# Thermistor.net
KiCad netlist of a schematic drawn in Altium Designer
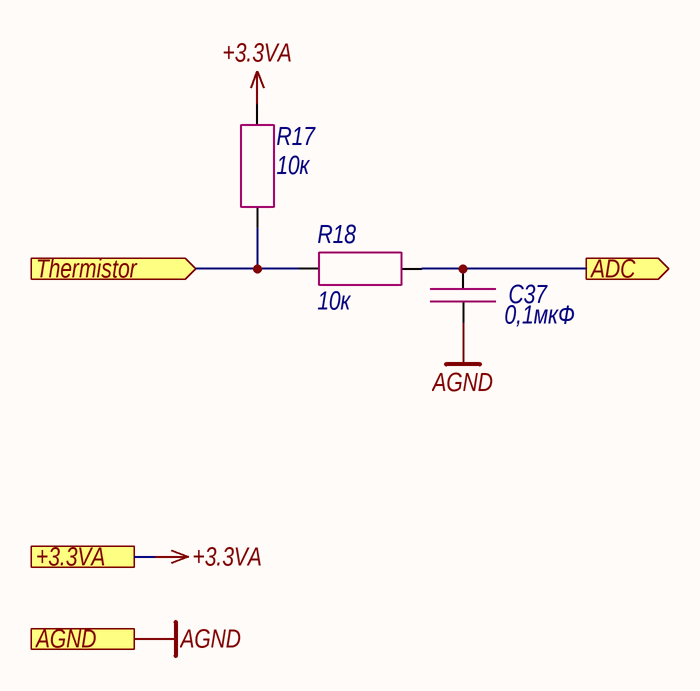
[diagram p0: Thermistor.SchDoc]

(export (version "E")
  (design (tool "Eeschema 10.0.6"))
  (components
    (comp (ref "C37")
      (value "0,1мкФ")
      (footprint "Pcb_library:CAP_0603")
      (fields (field (name "MANUFACTURER") "Murata"))
      (libsource (lib "Schem_library") (part "Capacitor"))
    )
    (comp (ref "R17")
      (value "10к")
      (footprint "Pcb_library:RES_0603")
      (fields (field (name "MANUFACTURER") "Yageo"))
      (libsource (lib "Schem_library") (part "Resistor"))
    )
    (comp (ref "R18")
      (value "10к")
      (footprint "Pcb_library:RES_0603")
      (fields (field (name "MANUFACTURER") "Yageo"))
      (libsource (lib "Schem_library") (part "Resistor"))
    )
  )
  (nets
    (net (code "1") (name "+3.3VA") (class "Default")
      (node (ref "R17") (pin "1") (pinfunction "1_1") (pintype "passive"))
    )
    (net (code "2") (name "/ADC") (class "Default")
      (node (ref "C37") (pin "1") (pinfunction "1_1") (pintype "passive"))
      (node (ref "R18") (pin "2") (pinfunction "2_2") (pintype "passive"))
    )
    (net (code "3") (name "/Thermistor") (class "Default")
      (node (ref "R17") (pin "2") (pinfunction "2_2") (pintype "passive"))
      (node (ref "R18") (pin "1") (pinfunction "1_1") (pintype "passive"))
    )
    (net (code "4") (name "AGND") (class "Default")
      (node (ref "C37") (pin "2") (pinfunction "2_2") (pintype "passive"))
    )
  )
)
